# 90_CAN.net
KiCad netlist of a schematic drawn in Altium Designer
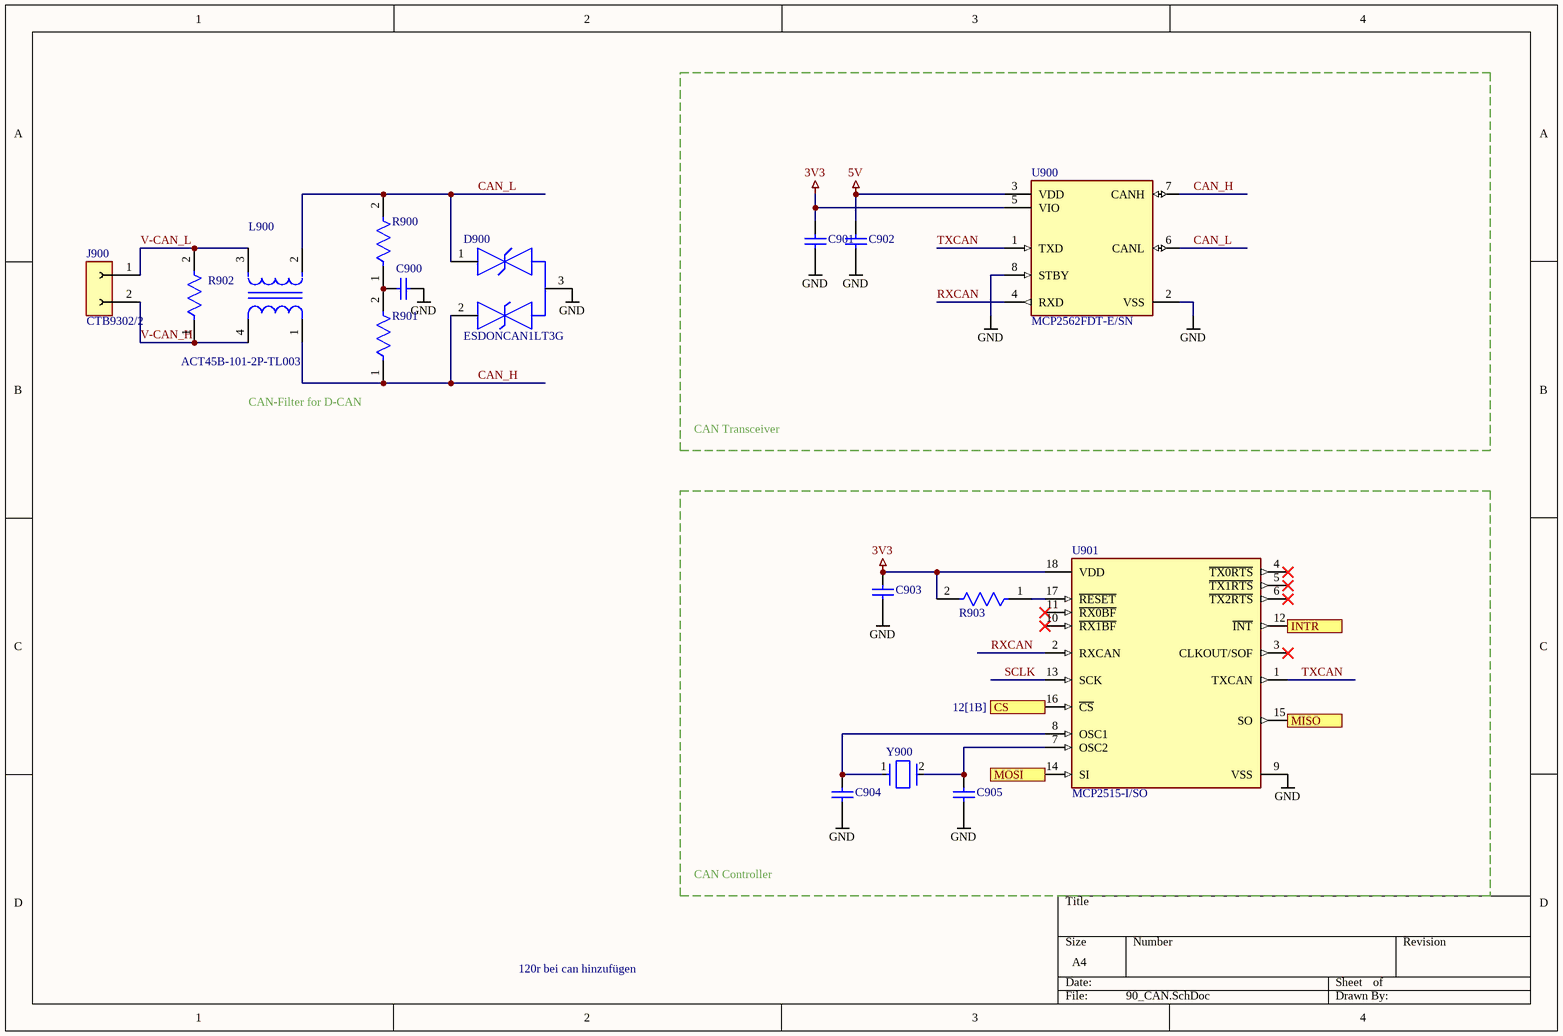
[diagram p0: 90_CAN.SchDoc]

(export (version "E")
  (design (tool "Eeschema 10.0.6"))
  (components
    (comp (ref "C900")
      (value "GRM188R71H472KA01D")
      (footprint "CAPC1608X90X35ML10T15")
      (fields (field (name "MANUFACTURER") "Murata"))
      (libsource (lib "Altium Content Vault") (part "CAP"))
    )
    (comp (ref "C901")
      (value "GRM188R71H104KA93D")
      (footprint "CAPC1608X90X35ML10T15")
      (description "Chip Capacitor, 0.1 uF, +/- 10%, 50 V, -55 to 125 degC, 0603 (1608 Metric), RoHS, Tape and Reel")
      (fields (field (name "TOLERANCE") "10%") (field (name "VOLTAGE") "50V"))
      (libsource (lib "Altium Content Vault") (part "CAP-NP-2"))
    )
    (comp (ref "C902")
      (value "GRM188R71H104KA93D")
      (footprint "CAPC1608X90X35ML10T15")
      (description "Chip Capacitor, 0.1 uF, +/- 10%, 50 V, -55 to 125 degC, 0603 (1608 Metric), RoHS, Tape and Reel")
      (fields (field (name "TOLERANCE") "10%") (field (name "VOLTAGE") "50V"))
      (libsource (lib "Altium Content Vault") (part "CAP-NP-2"))
    )
    (comp (ref "C903")
      (value "GRM188R71H104KA93D")
      (footprint "CAPC1608X90X35ML10T15")
      (description "Chip Capacitor, 0.1 uF, +/- 10%, 50 V, -55 to 125 degC, 0603 (1608 Metric), RoHS, Tape and Reel")
      (fields (field (name "TOLERANCE") "10%") (field (name "VOLTAGE") "50V"))
      (libsource (lib "Altium Content Vault") (part "CAP-NP-2"))
    )
    (comp (ref "C904")
      (value "GRM1885C1H220JA01D")
      (footprint "CAPC1608X90X35ML10T15")
      (description "Chip Capacitor, 22 pF, +/- 5%, 50 V, -55 to 125 degC, 0603 (1608 Metric), RoHS, Tape and Reel")
      (fields (field (name "MANUFACTURER") "Murata"))
      (libsource (lib "Altium Content Vault") (part "CAP-NP-2"))
    )
    (comp (ref "C905")
      (value "GRM1885C1H220JA01D")
      (footprint "CAPC1608X90X35ML10T15")
      (description "Chip Capacitor, 22 pF, +/- 5%, 50 V, -55 to 125 degC, 0603 (1608 Metric), RoHS, Tape and Reel")
      (fields (field (name "MANUFACTURER") "Murata"))
      (libsource (lib "Altium Content Vault") (part "CAP-NP-2"))
    )
    (comp (ref "D900")
      (value "ESDONCAN1LT3G")
      (footprint "FP-318-MFG")
      (description "ESDONCAN1LT3G ESD Suppressor TVS Dual Bi-Dir 3-Pin SOT-23 T/R - Tape and Reel")
      (libsource (lib "Altium Content Vault") (part "1bf5749f910b55743977e6066da6fbb"))
    )
    (comp (ref "J900")
      (value "CTB9302/2")
      (footprint "CTB9302-2")
      (description "CTB9302/2 - Stiftleiste - 2-pol, RM 5 mm, 0°")
      (libsource (lib "AltiumLib_MILUTIN") (part "CTB9302-2"))
    )
    (comp (ref "L900")
      (value "ACT45B-101-2P-TL003")
      (footprint "FP-ACT45B-MFG")
      (description "CMC 100UH 150MA 2LN SMD AEC-Q200")
      (fields
        (field (name "TOLERANCE") "+50/-30%")
        (field (name "OCTOPART") "https://octopart.com/act45b-101-2p-tl003-tdk-11353565")
      )
      (libsource (lib "Altium Content Vault") (part "7eaeb7798601bc1e7f00a291f87c402"))
    )
    (comp (ref "R900")
      (value "CRCW06034K70FKEA")
      (footprint "FP-CRCW0603-e3-IPC_A")
      (description "RES Thick Film, 4.7kΩ, 1%, 0.1W, 100ppm/°C, 0603")
      (fields (field (name "TOLERANCE") "1%"))
      (libsource (lib "Altium Content Vault") (part "1029c3af85768c4190bb7ad29bc67b5"))
    )
    (comp (ref "R901")
      (value "CRCW06034K70FKEA")
      (footprint "FP-CRCW0603-e3-IPC_A")
      (description "RES Thick Film, 4.7kΩ, 1%, 0.1W, 100ppm/°C, 0603")
      (fields (field (name "TOLERANCE") "1%"))
      (libsource (lib "Altium Content Vault") (part "1029c3af85768c4190bb7ad29bc67b5"))
    )
    (comp (ref "R902")
      (value "CRCW0603120RFKEA")
      (footprint "FP-CRCW0603-e3-MFG")
      (description "RES Thick Film, 120Ω, 1%, 0.1W, 100ppm/°C, 0603")
      (fields (field (name "TOLERANCE") "1%"))
      (libsource (lib "Altium Content Vault") (part "1029c3af85768c4190bb7ad29bc67b5"))
    )
    (comp (ref "R903")
      (value "CRCW06034K70FKEA")
      (footprint "FP-CRCW0603-e3-IPC_A")
      (description "RES Thick Film, 4.7kΩ, 1%, 0.1W, 100ppm/°C, 0603")
      (fields (field (name "TOLERANCE") "1%"))
      (libsource (lib "Altium Content Vault") (part "1029c3af85768c4190bb7ad29bc67b5"))
    )
    (comp (ref "U900")
      (value "MCP2562FDT-E/SN")
      (footprint "FP-C04-057-SN-MFG")
      (description "IC TRANSCEIVER 1/1 8SOIC")
      (libsource (lib "Altium Content Vault") (part "fcb6c66e4429206983adab9201371df"))
    )
    (comp (ref "U901")
      (value "MCP2515-I/SO")
      (footprint "FP-C04-051-MFG")
      (description "IC CAN CONTROLLER W/SPI 18SOIC")
      (fields
        (field (name "MANUFACTURER") "Microchip")
        (field (name "OCTOPART") "https://octopart.com/mcp2515-i%2Fso-microchip-430187")
      )
      (libsource (lib "Altium Content Vault") (part "1c78ea6ff576bac94664e2637e1b479"))
    )
    (comp (ref "Y900")
      (value "ABLS-16.000MHZ-K4T")
      (footprint "FP-ABLS-MFG")
      (description "CRYSTAL 16.0000MHZ 18PF SMD")
      (fields
        (field (name "TOLERANCE") "30ppm")
        (field (name "OCTOPART") "https://octopart.com/abls-16.000mhz-k4t-abracon-18618626")
      )
      (libsource (lib "Altium Content Vault") (part "c23a69dc6c9e2f18f2079038eb95dd1"))
    )
  )
  (nets
    (net (code "1") (name "/CAN_H") (class "Default")
      (node (ref "D900") (pin "2") (pinfunction "2_2") (pintype "passive"))
      (node (ref "L900") (pin "1") (pinfunction "1_1") (pintype "passive"))
      (node (ref "R901") (pin "1") (pinfunction "1_1") (pintype "passive"))
      (node (ref "U900") (pin "7") (pinfunction "CANH_7") (pintype "bidirectional"))
    )
    (net (code "2") (name "/CAN_L") (class "Default")
      (node (ref "D900") (pin "1") (pinfunction "1_1") (pintype "passive"))
      (node (ref "L900") (pin "2") (pinfunction "2_2") (pintype "passive"))
      (node (ref "R900") (pin "2") (pinfunction "2_2") (pintype "passive"))
      (node (ref "U900") (pin "6") (pinfunction "CANL_6") (pintype "bidirectional"))
    )
    (net (code "3") (name "/CS") (class "Default")
      (node (ref "U901") (pin "16") (pinfunction "~{CS}_16") (pintype "input"))
    )
    (net (code "4") (name "/INTR") (class "Default")
      (node (ref "U901") (pin "12") (pinfunction "~{INT}_12") (pintype "output"))
    )
    (net (code "5") (name "/MISO") (class "Default")
      (node (ref "U901") (pin "15") (pinfunction "SO_15") (pintype "output"))
    )
    (net (code "6") (name "/MOSI") (class "Default")
      (node (ref "U901") (pin "14") (pinfunction "SI_14") (pintype "input"))
    )
    (net (code "7") (name "/RXCAN") (class "Default")
      (node (ref "U900") (pin "4") (pinfunction "RXD_4") (pintype "output"))
      (node (ref "U901") (pin "2") (pinfunction "RXCAN_2") (pintype "input"))
    )
    (net (code "8") (name "/SCLK") (class "Default")
      (node (ref "U901") (pin "13") (pinfunction "SCK_13") (pintype "input"))
    )
    (net (code "9") (name "/TXCAN") (class "Default")
      (node (ref "U900") (pin "1") (pinfunction "TXD_1") (pintype "input"))
      (node (ref "U901") (pin "1") (pinfunction "TXCAN_1") (pintype "output"))
    )
    (net (code "10") (name "/V-CAN_H") (class "Default")
      (node (ref "J900") (pin "2") (pinfunction "2_2") (pintype "power_in"))
      (node (ref "L900") (pin "4") (pinfunction "4_4") (pintype "passive"))
      (node (ref "R902") (pin "1") (pinfunction "1_1") (pintype "passive"))
    )
    (net (code "11") (name "/V-CAN_L") (class "Default")
      (node (ref "J900") (pin "1") (pinfunction "1_1") (pintype "power_in"))
      (node (ref "L900") (pin "3") (pinfunction "3_3") (pintype "passive"))
      (node (ref "R902") (pin "2") (pinfunction "2_2") (pintype "passive"))
    )
    (net (code "12") (name "3V3") (class "Default")
      (node (ref "C901") (pin "2") (pinfunction "2_2") (pintype "passive"))
      (node (ref "C903") (pin "2") (pinfunction "2_2") (pintype "passive"))
      (node (ref "R903") (pin "2") (pinfunction "2_2") (pintype "passive"))
      (node (ref "U900") (pin "5") (pinfunction "VIO_5") (pintype "power_in"))
      (node (ref "U901") (pin "18") (pinfunction "VDD_18") (pintype "power_in"))
    )
    (net (code "13") (name "5V") (class "Default")
      (node (ref "C902") (pin "2") (pinfunction "2_2") (pintype "passive"))
      (node (ref "U900") (pin "3") (pinfunction "VDD_3") (pintype "power_in"))
    )
    (net (code "14") (name "GND") (class "Default")
      (node (ref "C900") (pin "2") (pinfunction "2_2") (pintype "passive"))
      (node (ref "C901") (pin "1") (pinfunction "1_1") (pintype "passive"))
      (node (ref "C902") (pin "1") (pinfunction "1_1") (pintype "passive"))
      (node (ref "C903") (pin "1") (pinfunction "1_1") (pintype "passive"))
      (node (ref "C904") (pin "1") (pinfunction "1_1") (pintype "passive"))
      (node (ref "C905") (pin "1") (pinfunction "1_1") (pintype "passive"))
      (node (ref "D900") (pin "3") (pinfunction "3_3") (pintype "passive"))
      (node (ref "U900") (pin "2") (pinfunction "VSS_2") (pintype "power_in"))
      (node (ref "U900") (pin "8") (pinfunction "STBY_8") (pintype "input"))
      (node (ref "U901") (pin "9") (pinfunction "VSS_9") (pintype "power_in"))
    )
    (net (code "15") (name "Net-(C900-Pad1)") (class "Default")
      (node (ref "C900") (pin "1") (pinfunction "1_1") (pintype "passive"))
      (node (ref "R900") (pin "1") (pinfunction "1_1") (pintype "passive"))
      (node (ref "R901") (pin "2") (pinfunction "2_2") (pintype "passive"))
    )
    (net (code "16") (name "Net-(U901-OSC1)") (class "Default")
      (node (ref "C904") (pin "2") (pinfunction "2_2") (pintype "passive"))
      (node (ref "U901") (pin "8") (pinfunction "OSC1_8") (pintype "input"))
      (node (ref "Y900") (pin "1") (pinfunction "1_1") (pintype "passive"))
    )
    (net (code "17") (name "Net-(U901-OSC2)") (class "Default")
      (node (ref "C905") (pin "2") (pinfunction "2_2") (pintype "passive"))
      (node (ref "U901") (pin "7") (pinfunction "OSC2_7") (pintype "input"))
      (node (ref "Y900") (pin "2") (pinfunction "2_2") (pintype "passive"))
    )
    (net (code "18") (name "Net-(U901-~{RESET})") (class "Default")
      (node (ref "R903") (pin "1") (pinfunction "1_1") (pintype "passive"))
      (node (ref "U901") (pin "17") (pinfunction "~{RESET}_17") (pintype "input"))
    )
    (net (code "19") (name "unconnected-(U901-CLKOUT{slash}SOF-Pad3)") (class "Default")
      (node (ref "U901") (pin "3") (pinfunction "CLKOUT/SOF_3") (pintype "output+no_connect"))
    )
    (net (code "20") (name "unconnected-(U901-~{RX0BF}-Pad11)") (class "Default")
      (node (ref "U901") (pin "11") (pinfunction "~{RX0BF}_11") (pintype "input+no_connect"))
    )
    (net (code "21") (name "unconnected-(U901-~{RX1BF}-Pad10)") (class "Default")
      (node (ref "U901") (pin "10") (pinfunction "~{RX1BF}_10") (pintype "input+no_connect"))
    )
    (net (code "22") (name "unconnected-(U901-~{TX0RTS}-Pad4)") (class "Default")
      (node (ref "U901") (pin "4") (pinfunction "~{TX0RTS}_4") (pintype "output+no_connect"))
    )
    (net (code "23") (name "unconnected-(U901-~{TX1RTS}-Pad5)") (class "Default")
      (node (ref "U901") (pin "5") (pinfunction "~{TX1RTS}_5") (pintype "output+no_connect"))
    )
    (net (code "24") (name "unconnected-(U901-~{TX2RTS}-Pad6)") (class "Default")
      (node (ref "U901") (pin "6") (pinfunction "~{TX2RTS}_6") (pintype "output+no_connect"))
    )
  )
)
